# headphone-detection-rev-a.net
KiCad netlist of a schematic drawn in EAGLE
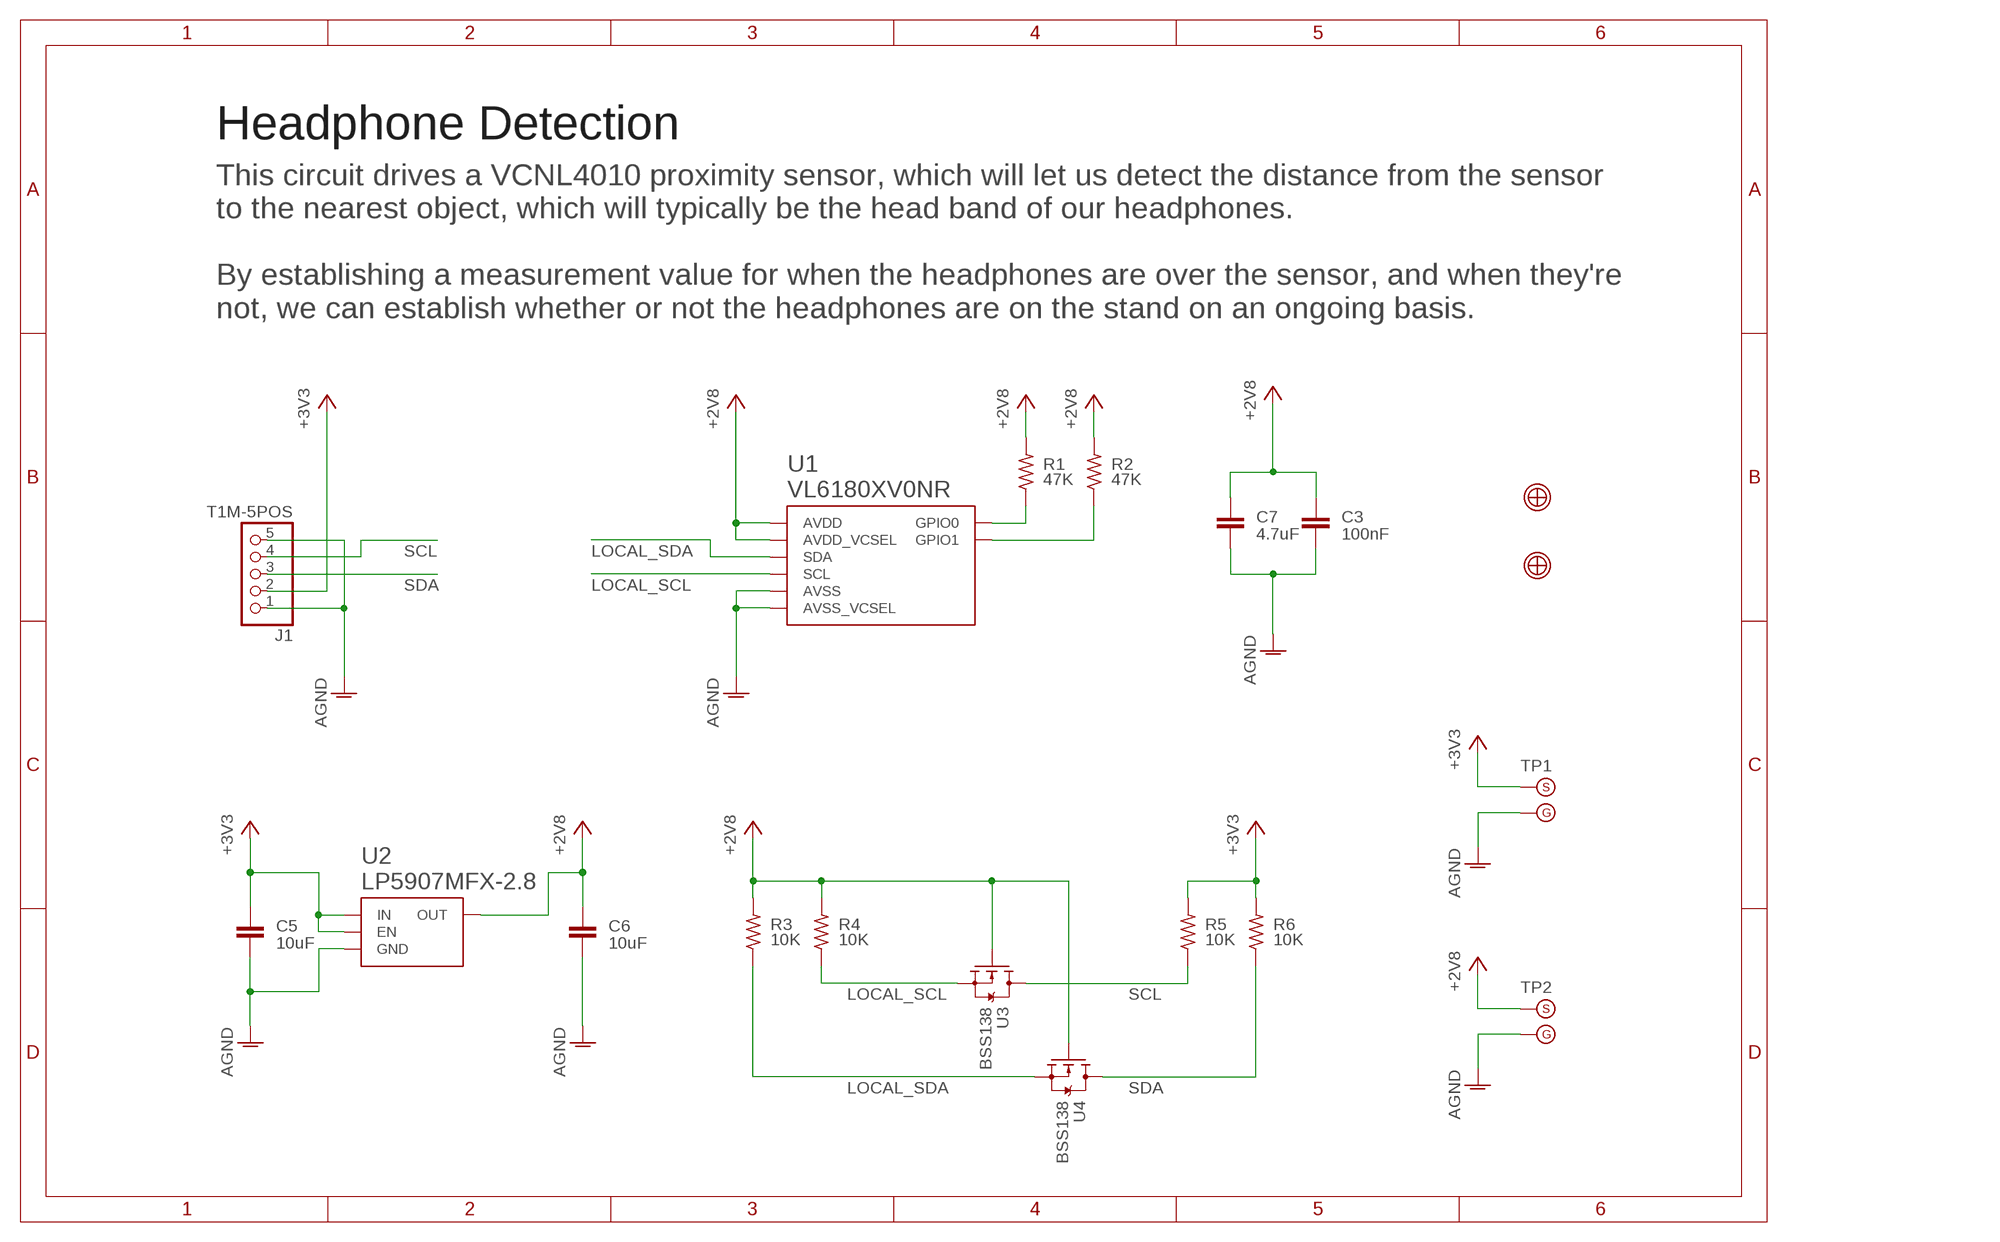
[diagram p0: schematic, sheet 1]

(export (version "E")
  (design (tool "Eeschema 10.0.6"))
  (components
    (comp (ref "C3")
      (value "100nF")
      (footprint "eagle-import:C0402")
      (libsource (lib "eagle-import") (part "CAPACITOR-0402"))
    )
    (comp (ref "C5")
      (value "10uF")
      (footprint "eagle-import:C0603")
      (libsource (lib "eagle-import") (part "CAPACITOR-0603"))
    )
    (comp (ref "C6")
      (value "10uF")
      (footprint "eagle-import:C0603")
      (libsource (lib "eagle-import") (part "CAPACITOR-0603"))
    )
    (comp (ref "C7")
      (value "4.7uF")
      (footprint "eagle-import:C0402")
      (libsource (lib "eagle-import") (part "CAPACITOR-0402"))
    )
    (comp (ref "J1")
      (value "T1M-5POS")
      (footprint "eagle-import:T1M-SINGLE-5POS")
      (libsource (lib "eagle-import") (part "T1M-5POS"))
    )
    (comp (ref "R1")
      (value "47K")
      (footprint "eagle-import:R0402")
      (libsource (lib "eagle-import") (part "RESISTOR-0402"))
    )
    (comp (ref "R2")
      (value "47K")
      (footprint "eagle-import:R0402")
      (libsource (lib "eagle-import") (part "RESISTOR-0402"))
    )
    (comp (ref "R3")
      (value "10K")
      (footprint "eagle-import:R0402")
      (libsource (lib "eagle-import") (part "RESISTOR-0402"))
    )
    (comp (ref "R4")
      (value "10K")
      (footprint "eagle-import:R0402")
      (libsource (lib "eagle-import") (part "RESISTOR-0402"))
    )
    (comp (ref "R5")
      (value "10K")
      (footprint "eagle-import:R0402")
      (libsource (lib "eagle-import") (part "RESISTOR-0402"))
    )
    (comp (ref "R6")
      (value "10K")
      (footprint "eagle-import:R0402")
      (libsource (lib "eagle-import") (part "RESISTOR-0402"))
    )
    (comp (ref "TP1")
      (value "TESTPOINT-WITH-GND")
      (footprint "eagle-import:TESTPOINT-1.5-WITH-GND")
      (libsource (lib "eagle-import") (part "TESTPOINT-WITH-GND"))
    )
    (comp (ref "TP2")
      (value "TESTPOINT-WITH-GND")
      (footprint "eagle-import:TESTPOINT-1.5-WITH-GND")
      (libsource (lib "eagle-import") (part "TESTPOINT-WITH-GND"))
    )
    (comp (ref "U$1")
      (value "FIDUCIAL-1MM")
      (footprint "eagle-import:FIDUCIAL_1MM")
      (libsource (lib "eagle-import") (part "FIDUCIAL-1MM"))
    )
    (comp (ref "U$2")
      (value "FIDUCIAL-1MM")
      (footprint "eagle-import:FIDUCIAL_1MM")
      (libsource (lib "eagle-import") (part "FIDUCIAL-1MM"))
    )
    (comp (ref "U1")
      (value "VL6180XV0NR")
      (footprint "eagle-import:VL6180X")
      (libsource (lib "eagle-import") (part "VL6180XV0NR"))
    )
    (comp (ref "U2")
      (value "LP5907MFX-2.8")
      (footprint "eagle-import:R-PDSO-G5-DBV")
      (libsource (lib "eagle-import") (part "LP5907MFX-2.8"))
    )
    (comp (ref "U3")
      (value "BSS138")
      (footprint "eagle-import:SOT23")
      (libsource (lib "eagle-import") (part "BSS138LT3G"))
    )
    (comp (ref "U4")
      (value "BSS138")
      (footprint "eagle-import:SOT23")
      (libsource (lib "eagle-import") (part "BSS138LT3G"))
    )
  )
  (nets
    (net (code "1") (name "+2V8") (class "Default")
      (node (ref "C3") (pin "1") (pinfunction "1_1") (pintype "passive"))
      (node (ref "C6") (pin "1") (pinfunction "1_1") (pintype "passive"))
      (node (ref "C7") (pin "1") (pinfunction "1_1") (pintype "passive"))
      (node (ref "R1") (pin "2") (pinfunction "2_2") (pintype "passive"))
      (node (ref "R2") (pin "2") (pinfunction "2_2") (pintype "passive"))
      (node (ref "R3") (pin "2") (pinfunction "2_2") (pintype "passive"))
      (node (ref "R4") (pin "2") (pinfunction "2_2") (pintype "passive"))
      (node (ref "TP2") (pin "S") (pinfunction "S_S") (pintype "bidirectional"))
      (node (ref "U1") (pin "10") (pinfunction "AVDD_10") (pintype "bidirectional"))
      (node (ref "U1") (pin "8") (pinfunction "AVDD_VCSEL_8") (pintype "bidirectional"))
      (node (ref "U2") (pin "5") (pinfunction "OUT_5") (pintype "bidirectional"))
      (node (ref "U3") (pin "1") (pinfunction "G_1") (pintype "passive"))
      (node (ref "U4") (pin "1") (pinfunction "G_1") (pintype "passive"))
    )
    (net (code "2") (name "+3V3") (class "Default")
      (node (ref "C5") (pin "1") (pinfunction "1_1") (pintype "passive"))
      (node (ref "J1") (pin "2") (pinfunction "2_2") (pintype "passive"))
      (node (ref "R5") (pin "2") (pinfunction "2_2") (pintype "passive"))
      (node (ref "R6") (pin "2") (pinfunction "2_2") (pintype "passive"))
      (node (ref "TP1") (pin "S") (pinfunction "S_S") (pintype "bidirectional"))
      (node (ref "U2") (pin "1") (pinfunction "IN_1") (pintype "bidirectional"))
      (node (ref "U2") (pin "3") (pinfunction "EN_3") (pintype "bidirectional"))
    )
    (net (code "3") (name "/LOCAL_SCL") (class "Default")
      (node (ref "R4") (pin "1") (pinfunction "1_1") (pintype "passive"))
      (node (ref "U1") (pin "5") (pinfunction "SCL_5") (pintype "bidirectional"))
      (node (ref "U3") (pin "2") (pinfunction "S_2") (pintype "passive"))
    )
    (net (code "4") (name "/LOCAL_SDA") (class "Default")
      (node (ref "R3") (pin "1") (pinfunction "1_1") (pintype "passive"))
      (node (ref "U1") (pin "6") (pinfunction "SDA_6") (pintype "bidirectional"))
      (node (ref "U4") (pin "2") (pinfunction "S_2") (pintype "passive"))
    )
    (net (code "5") (name "/SCL") (class "Default")
      (node (ref "J1") (pin "4") (pinfunction "4_4") (pintype "passive"))
      (node (ref "R5") (pin "1") (pinfunction "1_1") (pintype "passive"))
      (node (ref "U3") (pin "3") (pinfunction "D_3") (pintype "passive"))
    )
    (net (code "6") (name "/SDA") (class "Default")
      (node (ref "J1") (pin "3") (pinfunction "3_3") (pintype "passive"))
      (node (ref "R6") (pin "1") (pinfunction "1_1") (pintype "passive"))
      (node (ref "U4") (pin "3") (pinfunction "D_3") (pintype "passive"))
    )
    (net (code "7") (name "AGND") (class "Default")
      (node (ref "C3") (pin "2") (pinfunction "2_2") (pintype "passive"))
      (node (ref "C5") (pin "2") (pinfunction "2_2") (pintype "passive"))
      (node (ref "C6") (pin "2") (pinfunction "2_2") (pintype "passive"))
      (node (ref "C7") (pin "2") (pinfunction "2_2") (pintype "passive"))
      (node (ref "J1") (pin "1") (pinfunction "1_1") (pintype "passive"))
      (node (ref "J1") (pin "5") (pinfunction "5_5") (pintype "passive"))
      (node (ref "TP1") (pin "G") (pinfunction "G_G") (pintype "bidirectional"))
      (node (ref "TP2") (pin "G") (pinfunction "G_G") (pintype "bidirectional"))
      (node (ref "U1") (pin "12") (pinfunction "AVSS_12") (pintype "bidirectional"))
      (node (ref "U1") (pin "9") (pinfunction "AVSS_VCSEL_9") (pintype "bidirectional"))
      (node (ref "U2") (pin "2") (pinfunction "GND_2") (pintype "bidirectional"))
    )
    (net (code "8") (name "Net-(U1-GPIO0)") (class "Default")
      (node (ref "R1") (pin "1") (pinfunction "1_1") (pintype "passive"))
      (node (ref "U1") (pin "4") (pinfunction "GPIO0_4") (pintype "bidirectional"))
    )
    (net (code "9") (name "Net-(U1-GPIO1)") (class "Default")
      (node (ref "R2") (pin "1") (pinfunction "1_1") (pintype "passive"))
      (node (ref "U1") (pin "1") (pinfunction "GPIO1_1") (pintype "bidirectional"))
    )
  )
)
